# 4HP_Mixer.net
KiCad netlist of a schematic drawn in EAGLE
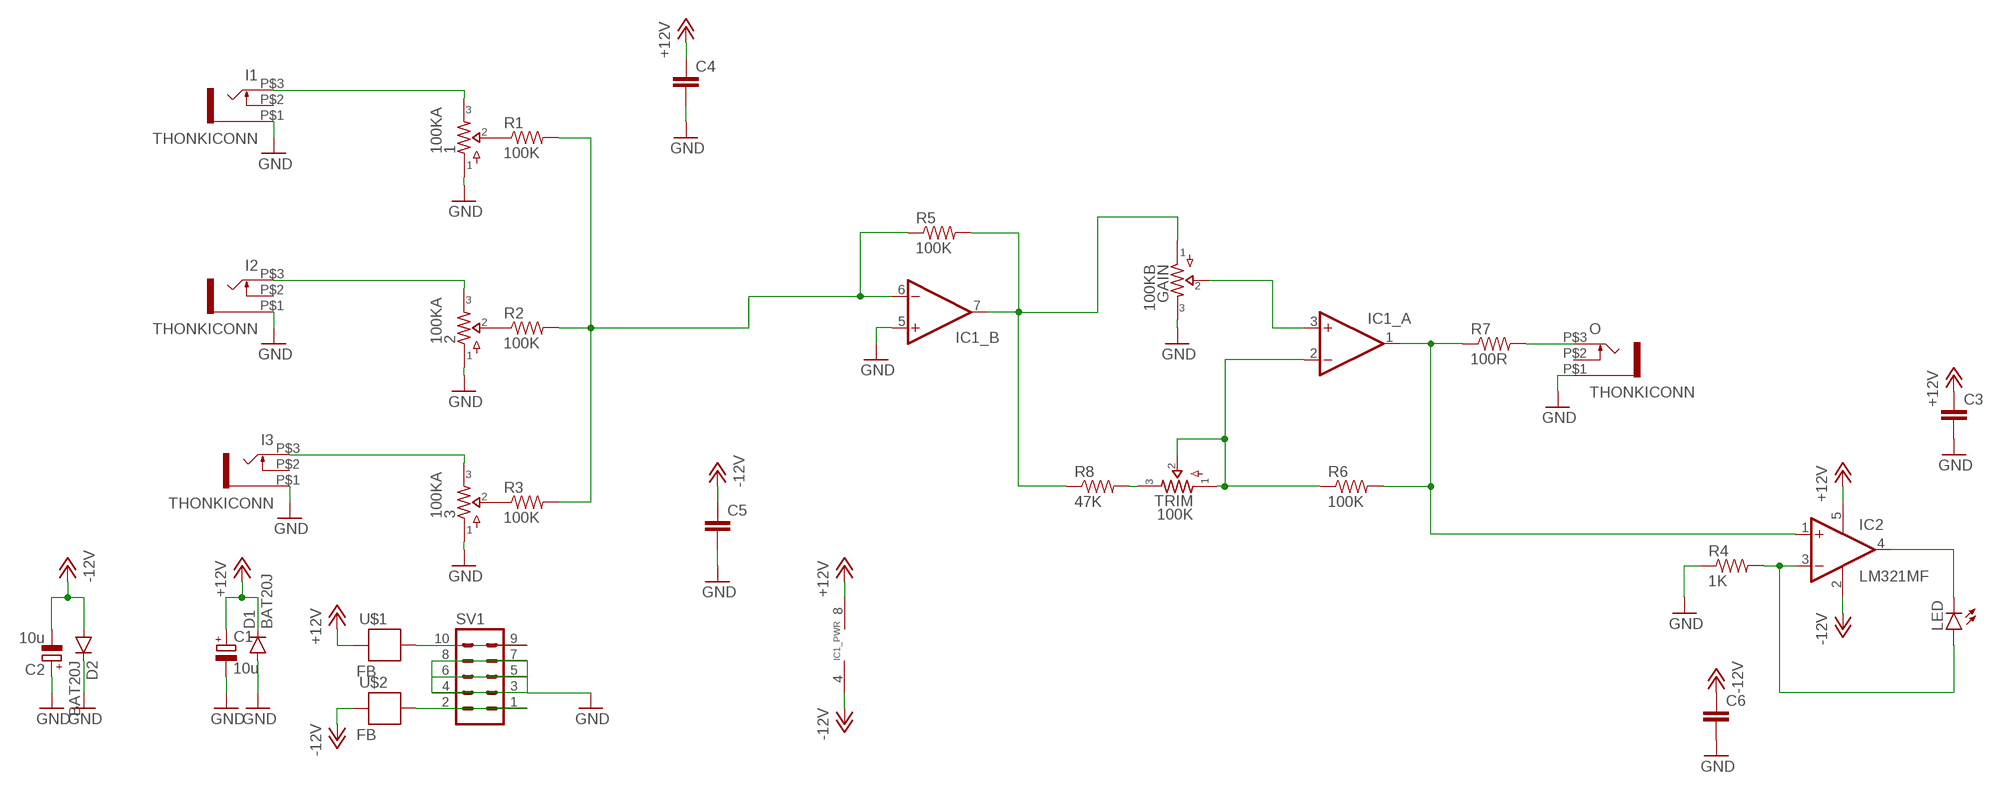
[diagram p0: schematic, sheet 1]

(export (version "E")
  (design (tool "Eeschema 10.0.6"))
  (components
    (comp (ref "1")
      (value "100KA")
      (footprint "eagle-import:9MM_W_MOUNTS-2MMHOLES")
      (libsource (lib "eagle-import") (part "POTS9MM_MOUNTED_2MMH"))
    )
    (comp (ref "2")
      (value "100KA")
      (footprint "eagle-import:9MM_W_MOUNTS-2MMHOLES")
      (libsource (lib "eagle-import") (part "POTS9MM_MOUNTED_2MMH"))
    )
    (comp (ref "3")
      (value "100KA")
      (footprint "eagle-import:9MM_W_MOUNTS-2MMHOLES")
      (libsource (lib "eagle-import") (part "POTS9MM_MOUNTED_2MMH"))
    )
    (comp (ref "C1")
      (value "10u")
      (footprint "eagle-import:CASE_B")
      (libsource (lib "eagle-import") (part "CAPACITOR_POL-CASE_B"))
    )
    (comp (ref "C2")
      (value "10u")
      (footprint "eagle-import:CASE_B")
      (libsource (lib "eagle-import") (part "CAPACITOR_POL-CASE_B"))
    )
    (comp (ref "C3")
      (value "CAP0603-CAP")
      (footprint "eagle-import:0603-CAP")
      (libsource (lib "eagle-import") (part "CAP0603-CAP"))
    )
    (comp (ref "C4")
      (value "CAP0603-CAP")
      (footprint "eagle-import:0603-CAP")
      (libsource (lib "eagle-import") (part "CAP0603-CAP"))
    )
    (comp (ref "C5")
      (value "CAP0603-CAP")
      (footprint "eagle-import:0603-CAP")
      (libsource (lib "eagle-import") (part "CAP0603-CAP"))
    )
    (comp (ref "C6")
      (value "CAP0603-CAP")
      (footprint "eagle-import:0603-CAP")
      (libsource (lib "eagle-import") (part "CAP0603-CAP"))
    )
    (comp (ref "D1")
      (value "BAT20J")
      (footprint "eagle-import:SOD-123")
      (libsource (lib "eagle-import") (part "DIODESOD123"))
    )
    (comp (ref "D2")
      (value "BAT20J")
      (footprint "eagle-import:SOD-123")
      (libsource (lib "eagle-import") (part "DIODESOD123"))
    )
    (comp (ref "GAIN")
      (value "100KB")
      (footprint "eagle-import:9MM_W_MOUNTS-2MMHOLES")
      (libsource (lib "eagle-import") (part "POTS9MM_MOUNTED_2MMH"))
    )
    (comp (ref "I1")
      (value "THONKICONN")
      (footprint "eagle-import:THONKICONN")
      (libsource (lib "eagle-import") (part "THONKICONN"))
    )
    (comp (ref "I2")
      (value "THONKICONN")
      (footprint "eagle-import:THONKICONN")
      (libsource (lib "eagle-import") (part "THONKICONN"))
    )
    (comp (ref "I3")
      (value "THONKICONN")
      (footprint "eagle-import:THONKICONN")
      (libsource (lib "eagle-import") (part "THONKICONN"))
    )
    (comp (ref "IC1")
      (value "DUALSMD")
      (footprint "eagle-import:SO08")
      (libsource (lib "eagle-import") (part "DUALSMD"))
    )
    (comp (ref "IC2")
      (value "LM321MF")
      (footprint "eagle-import:SOT23-5")
      (libsource (lib "eagle-import") (part "LM321?MF"))
    )
    (comp (ref "LED")
      (value "LED3MM")
      (footprint "eagle-import:LED3MM")
      (libsource (lib "eagle-import") (part "LED3MM"))
    )
    (comp (ref "O")
      (value "THONKICONN")
      (footprint "eagle-import:THONKICONN")
      (libsource (lib "eagle-import") (part "THONKICONN"))
    )
    (comp (ref "R1")
      (value "100K")
      (footprint "eagle-import:0603-RES")
      (libsource (lib "eagle-import") (part "RESISTOR0603-RES"))
    )
    (comp (ref "R2")
      (value "100K")
      (footprint "eagle-import:0603-RES")
      (libsource (lib "eagle-import") (part "RESISTOR0603-RES"))
    )
    (comp (ref "R3")
      (value "100K")
      (footprint "eagle-import:0603-RES")
      (libsource (lib "eagle-import") (part "RESISTOR0603-RES"))
    )
    (comp (ref "R4")
      (value "1K")
      (footprint "eagle-import:0603-RES")
      (libsource (lib "eagle-import") (part "RESISTOR0603-RES"))
    )
    (comp (ref "R5")
      (value "100K")
      (footprint "eagle-import:0603-RES")
      (libsource (lib "eagle-import") (part "RESISTOR0603-RES"))
    )
    (comp (ref "R6")
      (value "100K")
      (footprint "eagle-import:0603-RES")
      (libsource (lib "eagle-import") (part "RESISTOR0603-RES"))
    )
    (comp (ref "R7")
      (value "100R")
      (footprint "eagle-import:0603-RES")
      (libsource (lib "eagle-import") (part "RESISTOR0603-RES"))
    )
    (comp (ref "R8")
      (value "47K")
      (footprint "eagle-import:0603-RES")
      (libsource (lib "eagle-import") (part "RESISTOR0603-RES"))
    )
    (comp (ref "SV1")
      (value "EURO_POWER_HEADER")
      (footprint "eagle-import:EURO_POWER_HEADER")
      (libsource (lib "eagle-import") (part "EURO_POWER_HEADER"))
    )
    (comp (ref "TRIM")
      (value "100K")
      (footprint "eagle-import:PADS_SMALL")
      (libsource (lib "eagle-import") (part "POTSSMALL_PADS"))
    )
    (comp (ref "U$1")
      (value "FB")
      (footprint "eagle-import:0603")
      (libsource (lib "eagle-import") (part "FB"))
    )
    (comp (ref "U$2")
      (value "FB")
      (footprint "eagle-import:0603")
      (libsource (lib "eagle-import") (part "FB"))
    )
  )
  (nets
    (net (code "1") (name "+12V") (class "Default")
      (node (ref "C1") (pin "+") (pinfunction "+_+") (pintype "passive"))
      (node (ref "C3") (pin "1") (pinfunction "1_1") (pintype "passive"))
      (node (ref "C4") (pin "1") (pinfunction "1_1") (pintype "passive"))
      (node (ref "D1") (pin "C") (pinfunction "C_C") (pintype "passive"))
      (node (ref "IC1") (pin "8") (pinfunction "V+_8") (pintype "power_in"))
      (node (ref "IC2") (pin "5") (pinfunction "V+_5") (pintype "power_in"))
      (node (ref "U$1") (pin "2") (pinfunction "P$2_2") (pintype "bidirectional"))
    )
    (net (code "2") (name "-12V") (class "Default")
      (node (ref "C2") (pin "-") (pinfunction "-_-") (pintype "passive"))
      (node (ref "C5") (pin "1") (pinfunction "1_1") (pintype "passive"))
      (node (ref "C6") (pin "1") (pinfunction "1_1") (pintype "passive"))
      (node (ref "D2") (pin "A") (pinfunction "A_A") (pintype "passive"))
      (node (ref "IC1") (pin "4") (pinfunction "V-_4") (pintype "power_in"))
      (node (ref "IC2") (pin "2") (pinfunction "V-_2") (pintype "power_in"))
      (node (ref "U$2") (pin "2") (pinfunction "P$2_2") (pintype "bidirectional"))
    )
    (net (code "3") (name "GND") (class "Default")
      (node (ref "1") (pin "P$1") (pinfunction "1_P$1") (pintype "passive"))
      (node (ref "2") (pin "P$1") (pinfunction "1_P$1") (pintype "passive"))
      (node (ref "3") (pin "P$1") (pinfunction "1_P$1") (pintype "passive"))
      (node (ref "C1") (pin "-") (pinfunction "-_-") (pintype "passive"))
      (node (ref "C2") (pin "+") (pinfunction "+_+") (pintype "passive"))
      (node (ref "C3") (pin "2") (pinfunction "2_2") (pintype "passive"))
      (node (ref "C4") (pin "2") (pinfunction "2_2") (pintype "passive"))
      (node (ref "C5") (pin "2") (pinfunction "2_2") (pintype "passive"))
      (node (ref "C6") (pin "2") (pinfunction "2_2") (pintype "passive"))
      (node (ref "D1") (pin "A") (pinfunction "A_A") (pintype "passive"))
      (node (ref "D2") (pin "C") (pinfunction "C_C") (pintype "passive"))
      (node (ref "GAIN") (pin "P$3") (pinfunction "3_P$3") (pintype "passive"))
      (node (ref "I1") (pin "P$1") (pinfunction "5_P$1") (pintype "passive"))
      (node (ref "I2") (pin "P$1") (pinfunction "5_P$1") (pintype "passive"))
      (node (ref "I3") (pin "P$1") (pinfunction "5_P$1") (pintype "passive"))
      (node (ref "IC1") (pin "5") (pinfunction "+IN_5") (pintype "input"))
      (node (ref "O") (pin "P$1") (pinfunction "5_P$1") (pintype "passive"))
      (node (ref "R4") (pin "1") (pinfunction "1_1") (pintype "passive"))
      (node (ref "SV1") (pin "3") (pinfunction "3_3") (pintype "passive"))
      (node (ref "SV1") (pin "4") (pinfunction "4_4") (pintype "passive"))
      (node (ref "SV1") (pin "5") (pinfunction "5_5") (pintype "passive"))
      (node (ref "SV1") (pin "6") (pinfunction "6_6") (pintype "passive"))
      (node (ref "SV1") (pin "7") (pinfunction "7_7") (pintype "passive"))
      (node (ref "SV1") (pin "8") (pinfunction "8_8") (pintype "passive"))
    )
    (net (code "4") (name "Net-(1-2)") (class "Default")
      (node (ref "1") (pin "P$2") (pinfunction "2_P$2") (pintype "passive"))
      (node (ref "R1") (pin "1") (pinfunction "1_1") (pintype "passive"))
    )
    (net (code "5") (name "Net-(1-3)") (class "Default")
      (node (ref "1") (pin "P$3") (pinfunction "3_P$3") (pintype "passive"))
      (node (ref "I1") (pin "P$3") (pinfunction "3_P$3") (pintype "passive"))
    )
    (net (code "6") (name "Net-(2-2)") (class "Default")
      (node (ref "2") (pin "P$2") (pinfunction "2_P$2") (pintype "passive"))
      (node (ref "R2") (pin "1") (pinfunction "1_1") (pintype "passive"))
    )
    (net (code "7") (name "Net-(2-3)") (class "Default")
      (node (ref "2") (pin "P$3") (pinfunction "3_P$3") (pintype "passive"))
      (node (ref "I2") (pin "P$3") (pinfunction "3_P$3") (pintype "passive"))
    )
    (net (code "8") (name "Net-(3-2)") (class "Default")
      (node (ref "3") (pin "P$2") (pinfunction "2_P$2") (pintype "passive"))
      (node (ref "R3") (pin "1") (pinfunction "1_1") (pintype "passive"))
    )
    (net (code "9") (name "Net-(3-3)") (class "Default")
      (node (ref "3") (pin "P$3") (pinfunction "3_P$3") (pintype "passive"))
      (node (ref "I3") (pin "P$3") (pinfunction "3_P$3") (pintype "passive"))
    )
    (net (code "10") (name "Net-(GAIN-1)") (class "Default")
      (node (ref "GAIN") (pin "P$1") (pinfunction "1_P$1") (pintype "passive"))
      (node (ref "IC1") (pin "7") (pinfunction "OUT_7") (pintype "output"))
      (node (ref "R5") (pin "2") (pinfunction "2_2") (pintype "passive"))
      (node (ref "R8") (pin "1") (pinfunction "1_1") (pintype "passive"))
    )
    (net (code "11") (name "Net-(GAIN-2)") (class "Default")
      (node (ref "GAIN") (pin "P$2") (pinfunction "2_P$2") (pintype "passive"))
      (node (ref "IC1") (pin "3") (pinfunction "+IN_3") (pintype "input"))
    )
    (net (code "12") (name "Net-(IC1A--IN)") (class "Default")
      (node (ref "IC1") (pin "2") (pinfunction "-IN_2") (pintype "input"))
      (node (ref "R6") (pin "1") (pinfunction "1_1") (pintype "passive"))
      (node (ref "TRIM") (pin "1") (pinfunction "1_1") (pintype "passive"))
      (node (ref "TRIM") (pin "2") (pinfunction "2_2") (pintype "passive"))
    )
    (net (code "13") (name "Net-(IC1A-OUT)") (class "Default")
      (node (ref "IC1") (pin "1") (pinfunction "OUT_1") (pintype "output"))
      (node (ref "IC2") (pin "1") (pinfunction "+IN_1") (pintype "input"))
      (node (ref "R6") (pin "2") (pinfunction "2_2") (pintype "passive"))
      (node (ref "R7") (pin "1") (pinfunction "1_1") (pintype "passive"))
    )
    (net (code "14") (name "Net-(IC1B--IN)") (class "Default")
      (node (ref "IC1") (pin "6") (pinfunction "-IN_6") (pintype "input"))
      (node (ref "R1") (pin "2") (pinfunction "2_2") (pintype "passive"))
      (node (ref "R2") (pin "2") (pinfunction "2_2") (pintype "passive"))
      (node (ref "R3") (pin "2") (pinfunction "2_2") (pintype "passive"))
      (node (ref "R5") (pin "1") (pinfunction "1_1") (pintype "passive"))
    )
    (net (code "15") (name "Net-(IC2--IN)") (class "Default")
      (node (ref "IC2") (pin "3") (pinfunction "-IN_3") (pintype "input"))
      (node (ref "LED") (pin "A") (pinfunction "A_A") (pintype "passive"))
      (node (ref "R4") (pin "2") (pinfunction "2_2") (pintype "passive"))
    )
    (net (code "16") (name "Net-(IC2-OUT)") (class "Default")
      (node (ref "IC2") (pin "4") (pinfunction "OUT_4") (pintype "output"))
      (node (ref "LED") (pin "K") (pinfunction "C_K") (pintype "passive"))
    )
    (net (code "17") (name "Net-(O-3)") (class "Default")
      (node (ref "O") (pin "P$3") (pinfunction "3_P$3") (pintype "passive"))
      (node (ref "R7") (pin "2") (pinfunction "2_2") (pintype "passive"))
    )
    (net (code "18") (name "Net-(R8-Pad2)") (class "Default")
      (node (ref "R8") (pin "2") (pinfunction "2_2") (pintype "passive"))
      (node (ref "TRIM") (pin "3") (pinfunction "3_3") (pintype "passive"))
    )
    (net (code "19") (name "Net-(U$1-P$1)") (class "Default")
      (node (ref "SV1") (pin "10") (pinfunction "10_10") (pintype "passive"))
      (node (ref "SV1") (pin "9") (pinfunction "9_9") (pintype "passive"))
      (node (ref "U$1") (pin "1") (pinfunction "P$1_1") (pintype "bidirectional"))
    )
    (net (code "20") (name "Net-(U$2-P$1)") (class "Default")
      (node (ref "SV1") (pin "1") (pinfunction "1_1") (pintype "passive"))
      (node (ref "SV1") (pin "2") (pinfunction "2_2") (pintype "passive"))
      (node (ref "U$2") (pin "1") (pinfunction "P$1_1") (pintype "bidirectional"))
    )
    (net (code "21") (name "unconnected-(I1-4-PadP$2)") (class "Default")
      (node (ref "I1") (pin "P$2") (pinfunction "4_P$2") (pintype "passive"))
    )
    (net (code "22") (name "unconnected-(I2-4-PadP$2)") (class "Default")
      (node (ref "I2") (pin "P$2") (pinfunction "4_P$2") (pintype "passive"))
    )
    (net (code "23") (name "unconnected-(I3-4-PadP$2)") (class "Default")
      (node (ref "I3") (pin "P$2") (pinfunction "4_P$2") (pintype "passive"))
    )
    (net (code "24") (name "unconnected-(O-4-PadP$2)") (class "Default")
      (node (ref "O") (pin "P$2") (pinfunction "4_P$2") (pintype "passive"))
    )
  )
)
